# Motor-E2.net
KiCad netlist of a schematic drawn in Altium Designer
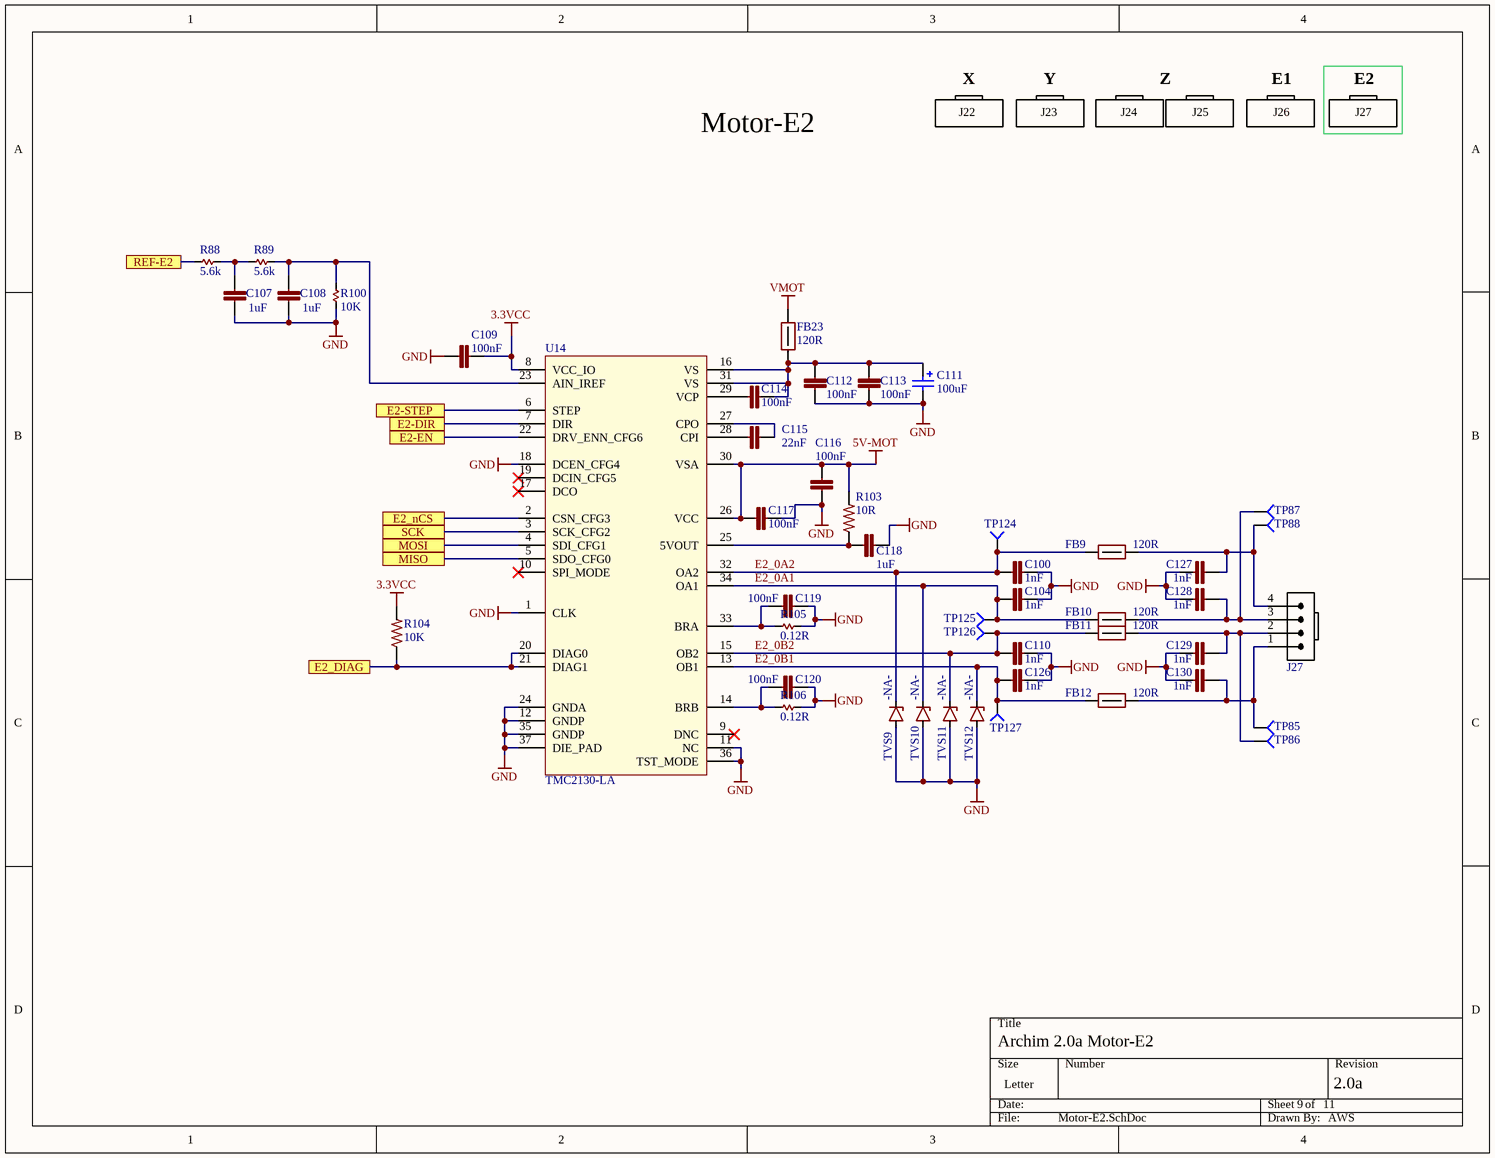
[diagram p0: Motor-E2.SchDoc]

(export (version "E")
  (design (tool "Eeschema 10.0.6"))
  (components
    (comp (ref "C100")
      (value "1nF")
      (footprint "C0402")
      (description "1000pF 50V Ceramic Capacitor X7R 0402 (1005 Metric) 0.039\" L x 0.020\" W (1.00mm x 0.50mm)")
      (fields (field (name "MANUFACTURER") "Murata") (field (name "PART") "1nF 50V X7R 0402"))
      (libsource (lib "3Delight") (part "CAP 1nF 50V 0402 X7R"))
    )
    (comp (ref "C104")
      (value "1nF")
      (footprint "C0402")
      (description "1000pF 50V Ceramic Capacitor X7R 0402 (1005 Metric) 0.039\" L x 0.020\" W (1.00mm x 0.50mm)")
      (fields (field (name "MANUFACTURER") "Murata") (field (name "PART") "1nF 50V X7R 0402"))
      (libsource (lib "3Delight") (part "CAP 1nF 50V 0402 X7R"))
    )
    (comp (ref "C107")
      (value "1uF")
      (footprint "C0402")
      (description "CAP CER 0402 1uF 6.3V 10% X5R")
      (fields (field (name "MANUFACTURER") "Murata") (field (name "PART") "1uF 6.3V X5R 0402"))
      (libsource (lib "") (part "GRM155R60J105KE19D_1"))
    )
    (comp (ref "C108")
      (value "1uF")
      (footprint "C0402")
      (description "CAP CER 0402 1uF 6.3V 10% X5R")
      (fields (field (name "MANUFACTURER") "Murata") (field (name "PART") "1uF 6.3V X5R 0402"))
      (libsource (lib "") (part "GRM155R60J105KE19D_1"))
    )
    (comp (ref "C109")
      (value "100nF")
      (footprint "C0402")
      (description "CAP CER 0402 100nF 16V 10% X7R")
      (fields (field (name "MANUFACTURER") "Murata") (field (name "PART") "0.1uF 16V X7R 0402"))
      (libsource (lib "") (part "GRM155R71C104KA88D_1"))
    )
    (comp (ref "C110")
      (value "1nF")
      (footprint "C0402")
      (description "1000pF 50V Ceramic Capacitor X7R 0402 (1005 Metric) 0.039\" L x 0.020\" W (1.00mm x 0.50mm)")
      (fields (field (name "MANUFACTURER") "Murata") (field (name "PART") "1nF 50V X7R 0402"))
      (libsource (lib "3Delight") (part "CAP 1nF 50V 0402 X7R"))
    )
    (comp (ref "C111")
      (value "100uF")
      (footprint "CAP-ELEC-063063077")
      (description "CAP ALUM 100UF 35V 20% SMD")
      (fields (field (name "MANUFACTURER") "Nichicon") (field (name "PART") "100uF 35V SMD Al-El"))
      (libsource (lib "3Delight") (part "UWT1V101MCL1GS"))
    )
    (comp (ref "C112")
      (value "100nF")
      (footprint "C0603")
      (description "CAP CER 0603 100nF 50V 10% X7R")
      (fields (field (name "MANUFACTURER") "Kemet") (field (name "PART") "100nF 50V X7R 0603"))
      (libsource (lib "3Delight") (part "C0603C104K5RACTU"))
    )
    (comp (ref "C113")
      (value "100nF")
      (footprint "C0603")
      (description "CAP CER 0603 100nF 50V 10% X7R")
      (fields (field (name "MANUFACTURER") "Kemet") (field (name "PART") "100nF 50V X7R 0603"))
      (libsource (lib "3Delight") (part "C0603C104K5RACTU"))
    )
    (comp (ref "C114")
      (value "100nF")
      (footprint "C0603")
      (description "CAP CER 0603 100nF 50V 10% X7R")
      (fields (field (name "MANUFACTURER") "Kemet") (field (name "PART") "100nF 50V X7R 0603"))
      (libsource (lib "") (part "C0603C104K5RACTU_1"))
    )
    (comp (ref "C115")
      (value "22nF")
      (footprint "C0402")
      (description "CAP CER 0402 22nF ±10% 50V X7R")
      (fields (field (name "MANUFACTURER") "YAGEO") (field (name "TOLERANCE") "+/- 10%"))
      (libsource (lib "3Delight") (part "GCM155R71H223KA55D"))
    )
    (comp (ref "C116")
      (value "100nF")
      (footprint "C0402")
      (description "CAP CER 0402 100nF 16V 10% X7R")
      (fields (field (name "MANUFACTURER") "Murata") (field (name "PART") "0.1uF 16V X7R 0402"))
      (libsource (lib "3Delight") (part "GRM155R71C104KA88D"))
    )
    (comp (ref "C117")
      (value "100nF")
      (footprint "C0402")
      (description "CAP CER 0402 100nF 16V 10% X7R")
      (fields (field (name "MANUFACTURER") "Murata") (field (name "PART") "0.1uF 16V X7R 0402"))
      (libsource (lib "") (part "GRM155R71C104KA88D_1"))
    )
    (comp (ref "C118")
      (value "1uF")
      (footprint "C0402")
      (description "CAP CER 0402 1uF 6.3V 10% X5R")
      (fields (field (name "MANUFACTURER") "Murata") (field (name "PART") "1uF 6.3V X5R 0402"))
      (libsource (lib "3Delight") (part "GRM155R60J105KE19D"))
    )
    (comp (ref "C119")
      (value "100nF")
      (footprint "C0603")
      (description "CAP CER 0603 100nF 50V 10% X7R")
      (fields (field (name "MANUFACTURER") "Kemet") (field (name "PART") "100nF 50V X7R 0603"))
      (libsource (lib "") (part "C0603C104K5RACTU_2"))
    )
    (comp (ref "C120")
      (value "100nF")
      (footprint "C0603")
      (description "CAP CER 0603 100nF 50V 10% X7R")
      (fields (field (name "MANUFACTURER") "Kemet") (field (name "PART") "100nF 50V X7R 0603"))
      (libsource (lib "") (part "C0603C104K5RACTU_2"))
    )
    (comp (ref "C126")
      (value "1nF")
      (footprint "C0402")
      (description "1000pF 50V Ceramic Capacitor X7R 0402 (1005 Metric) 0.039\" L x 0.020\" W (1.00mm x 0.50mm)")
      (fields (field (name "MANUFACTURER") "Murata") (field (name "PART") "1nF 50V X7R 0402"))
      (libsource (lib "3Delight") (part "CAP 1nF 50V 0402 X7R"))
    )
    (comp (ref "C127")
      (value "1nF")
      (footprint "C0402")
      (description "1000pF 50V Ceramic Capacitor X7R 0402 (1005 Metric) 0.039\" L x 0.020\" W (1.00mm x 0.50mm)")
      (fields (field (name "MANUFACTURER") "Murata") (field (name "PART") "1nF 50V X7R 0402"))
      (libsource (lib "3Delight") (part "CAP 1nF 50V 0402 X7R"))
    )
    (comp (ref "C128")
      (value "1nF")
      (footprint "C0402")
      (description "1000pF 50V Ceramic Capacitor X7R 0402 (1005 Metric) 0.039\" L x 0.020\" W (1.00mm x 0.50mm)")
      (fields (field (name "MANUFACTURER") "Murata") (field (name "PART") "1nF 50V X7R 0402"))
      (libsource (lib "3Delight") (part "CAP 1nF 50V 0402 X7R"))
    )
    (comp (ref "C129")
      (value "1nF")
      (footprint "C0402")
      (description "1000pF 50V Ceramic Capacitor X7R 0402 (1005 Metric) 0.039\" L x 0.020\" W (1.00mm x 0.50mm)")
      (fields (field (name "MANUFACTURER") "Murata") (field (name "PART") "1nF 50V X7R 0402"))
      (libsource (lib "3Delight") (part "CAP 1nF 50V 0402 X7R"))
    )
    (comp (ref "C130")
      (value "1nF")
      (footprint "C0402")
      (description "1000pF 50V Ceramic Capacitor X7R 0402 (1005 Metric) 0.039\" L x 0.020\" W (1.00mm x 0.50mm)")
      (fields (field (name "MANUFACTURER") "Murata") (field (name "PART") "1nF 50V X7R 0402"))
      (libsource (lib "3Delight") (part "CAP 1nF 50V 0402 X7R"))
    )
    (comp (ref "FB9")
      (value "120R")
      (footprint "FB0603")
      (description "FERRITE BEAD 120 OHM 0603 1LN")
      (fields (field (name "MANUFACTURER") "Samsung") (field (name "PART") "FERRITE 120R 3A 0603"))
      (libsource (lib "3Delight") (part "FERRITE 220R 2.5A 0603"))
    )
    (comp (ref "FB10")
      (value "120R")
      (footprint "FB0603")
      (description "FERRITE BEAD 120 OHM 0603 1LN")
      (fields (field (name "MANUFACTURER") "Samsung") (field (name "PART") "FERRITE 120R 3A 0603"))
      (libsource (lib "3Delight") (part "FERRITE 220R 2.5A 0603"))
    )
    (comp (ref "FB11")
      (value "120R")
      (footprint "FB0603")
      (description "FERRITE BEAD 120 OHM 0603 1LN")
      (fields (field (name "MANUFACTURER") "Samsung") (field (name "PART") "FERRITE 120R 3A 0603"))
      (libsource (lib "3Delight") (part "FERRITE 220R 2.5A 0603"))
    )
    (comp (ref "FB12")
      (value "120R")
      (footprint "FB0603")
      (description "FERRITE BEAD 120 OHM 0603 1LN")
      (fields (field (name "MANUFACTURER") "Samsung") (field (name "PART") "FERRITE 120R 3A 0603"))
      (libsource (lib "3Delight") (part "FERRITE 220R 2.5A 0603"))
    )
    (comp (ref "FB23")
      (value "120R")
      (footprint "FB0603")
      (description "FERRITE BEAD 120 OHM 0603 1LN")
      (fields (field (name "MANUFACTURER") "Samsung") (field (name "PART") "FERRITE 120R 3A 0603"))
      (libsource (lib "Inductors") (part "FERRITE 120R 3A 0603"))
    )
    (comp (ref "J27")
      (value "Molex 0705430038")
      (footprint "4POL254 PIN-IN-PASTE")
      (description "Molex 4 Pin Clip Connector - Pin In Paste footprint")
      (libsource (lib "Connectors") (part "Molex 0705430003 PIP"))
    )
    (comp (ref "R88")
      (value "5.6k")
      (footprint "R0402")
      (description "RES SMD 5.6K OHM 1% 1/16W 0402")
      (fields (field (name "MANUFACTURER") "YAGEO") (field (name "TOLERANCE") "1%"))
      (libsource (lib "Resistors") (part "5.6k 1% 0402"))
    )
    (comp (ref "R89")
      (value "5.6k")
      (footprint "R0402")
      (description "RES SMD 5.6K OHM 1% 1/16W 0402")
      (fields (field (name "MANUFACTURER") "YAGEO") (field (name "TOLERANCE") "1%"))
      (libsource (lib "Resistors") (part "5.6k 1% 0402"))
    )
    (comp (ref "R100")
      (value "10K")
      (footprint "R0402")
      (description "RES SMD 10K OHM 1% 1/16W 0402")
      (fields (field (name "MANUFACTURER") "Yageo") (field (name "PART") "10k 1% 0402"))
      (libsource (lib "Resistors") (part "10k 1% 0402"))
    )
    (comp (ref "R103")
      (value "10R")
      (footprint "R0402")
      (description "RES SMD 10 OHM 1% 1/16W 0402")
      (fields (field (name "MANUFACTURER") "Yageo") (field (name "TOLERANCE") "1%"))
      (libsource (lib "3Delight") (part "RC0402FR-0710RL"))
    )
    (comp (ref "R104")
      (value "10K")
      (footprint "R0402")
      (description "RES SMD 10K OHM 1% 1/16W 0402")
      (fields (field (name "MANUFACTURER") "Yageo") (field (name "PART") "10k 1% 0402"))
      (libsource (lib "3Delight") (part "RC0402FR-0710KP"))
    )
    (comp (ref "R105")
      (value "0.12R")
      (footprint "R1206")
      (description "RES 0.12 OHM 1% 1/2W 1206")
      (fields (field (name "TOLERANCE") "+/- 1%"))
      (libsource (lib "Resistors") (part "0.12R 1% 1206"))
    )
    (comp (ref "R106")
      (value "0.12R")
      (footprint "R1206")
      (description "RES 0.12 OHM 1% 1/2W 1206")
      (fields (field (name "TOLERANCE") "+/- 1%"))
      (libsource (lib "Resistors") (part "0.12R 1% 1206"))
    )
    (comp (ref "TP85")
      (value "TP4")
      (footprint "TP-2")
      (description "Socket")
      (libsource (lib "Archim") (part "Socket"))
    )
    (comp (ref "TP86")
      (value "TP4")
      (footprint "TP-2")
      (description "Socket")
      (libsource (lib "Archim") (part "Socket"))
    )
    (comp (ref "TP87")
      (value "TP4")
      (footprint "TP-2")
      (description "Socket")
      (libsource (lib "Archim") (part "Socket"))
    )
    (comp (ref "TP88")
      (value "TP4")
      (footprint "TP-2")
      (description "Socket")
      (libsource (lib "Archim") (part "Socket"))
    )
    (comp (ref "TP124")
      (value "TP4")
      (footprint "TP-2")
      (description "Socket")
      (libsource (lib "Archim") (part "Socket"))
    )
    (comp (ref "TP125")
      (value "TP4")
      (footprint "TP-2")
      (description "Socket")
      (libsource (lib "Archim") (part "Socket"))
    )
    (comp (ref "TP126")
      (value "TP4")
      (footprint "TP-2")
      (description "Socket")
      (libsource (lib "Archim") (part "Socket"))
    )
    (comp (ref "TP127")
      (value "TP4")
      (footprint "TP-2")
      (description "Socket")
      (libsource (lib "Archim") (part "Socket"))
    )
    (comp (ref "TVS9")
      (value "-NA-")
      (footprint "SMF")
      (description "TVS DIODE 30VWM 48.4VC SMF")
      (fields (field (name "MANUFACTURER") "Vishay") (field (name "PART") "TVS Diode 48.4VC"))
      (libsource (lib "3Delight") (part "TVS 30V SMF"))
    )
    (comp (ref "TVS10")
      (value "-NA-")
      (footprint "SMF")
      (description "TVS DIODE 30VWM 48.4VC SMF")
      (fields (field (name "MANUFACTURER") "Vishay") (field (name "PART") "TVS Diode 48.4VC"))
      (libsource (lib "3Delight") (part "TVS 30V SMF"))
    )
    (comp (ref "TVS11")
      (value "-NA-")
      (footprint "SMF")
      (description "TVS DIODE 30VWM 48.4VC SMF")
      (fields (field (name "MANUFACTURER") "Vishay") (field (name "PART") "TVS Diode 48.4VC"))
      (libsource (lib "3Delight") (part "TVS 30V SMF"))
    )
    (comp (ref "TVS12")
      (value "-NA-")
      (footprint "SMF")
      (description "TVS DIODE 30VWM 48.4VC SMF")
      (fields (field (name "MANUFACTURER") "Vishay") (field (name "PART") "TVS Diode 48.4VC"))
      (libsource (lib "3Delight") (part "TVS 30V SMF"))
    )
    (comp (ref "U14")
      (value "TMC2130-LA")
      (footprint "QFN36-50P500X600X900_HS-37N")
      (description "IC STEPPER MOTOR DVR SPI 36QFN")
      (fields (field (name "MANUFACTURER") "Trinamic") (field (name "PART") "TMC2130"))
      (libsource (lib "ICs-Motor Controller") (part "TMC2130-LA-T"))
    )
  )
  (nets
    (net (code "1") (name "/E2-DIR") (class "Default")
      (node (ref "U14") (pin "7") (pinfunction "DIR_7") (pintype "passive"))
    )
    (net (code "2") (name "/E2-EN") (class "Default")
      (node (ref "U14") (pin "22") (pinfunction "DRV_ENN_CFG6_22") (pintype "passive"))
    )
    (net (code "3") (name "/E2-STEP") (class "Default")
      (node (ref "U14") (pin "6") (pinfunction "STEP_6") (pintype "passive"))
    )
    (net (code "4") (name "/E2_0A1") (class "Default")
      (node (ref "C104") (pin "1") (pinfunction "1_1") (pintype "passive"))
      (node (ref "FB10") (pin "1") (pinfunction "1_1") (pintype "passive"))
      (node (ref "TP125") (pin "1") (pinfunction "1_1") (pintype "passive"))
      (node (ref "TVS10") (pin "K") (pinfunction "K_K") (pintype "passive"))
      (node (ref "U14") (pin "34") (pinfunction "OA1_34") (pintype "passive"))
    )
    (net (code "5") (name "/E2_0A2") (class "Default")
      (node (ref "C100") (pin "1") (pinfunction "1_1") (pintype "passive"))
      (node (ref "FB9") (pin "1") (pinfunction "1_1") (pintype "passive"))
      (node (ref "TP124") (pin "1") (pinfunction "1_1") (pintype "passive"))
      (node (ref "TVS9") (pin "K") (pinfunction "K_K") (pintype "passive"))
      (node (ref "U14") (pin "32") (pinfunction "OA2_32") (pintype "passive"))
    )
    (net (code "6") (name "/E2_0B1") (class "Default")
      (node (ref "C126") (pin "1") (pinfunction "1_1") (pintype "passive"))
      (node (ref "FB12") (pin "1") (pinfunction "1_1") (pintype "passive"))
      (node (ref "TP127") (pin "1") (pinfunction "1_1") (pintype "passive"))
      (node (ref "TVS12") (pin "K") (pinfunction "K_K") (pintype "passive"))
      (node (ref "U14") (pin "13") (pinfunction "OB1_13") (pintype "passive"))
    )
    (net (code "7") (name "/E2_0B2") (class "Default")
      (node (ref "C110") (pin "1") (pinfunction "1_1") (pintype "passive"))
      (node (ref "FB11") (pin "1") (pinfunction "1_1") (pintype "passive"))
      (node (ref "TP126") (pin "1") (pinfunction "1_1") (pintype "passive"))
      (node (ref "TVS11") (pin "K") (pinfunction "K_K") (pintype "passive"))
      (node (ref "U14") (pin "15") (pinfunction "OB2_15") (pintype "passive"))
    )
    (net (code "8") (name "/E2_DIAG") (class "Default")
      (node (ref "R104") (pin "1") (pinfunction "1_1") (pintype "passive"))
      (node (ref "U14") (pin "20") (pinfunction "DIAG0_20") (pintype "passive"))
      (node (ref "U14") (pin "21") (pinfunction "DIAG1_21") (pintype "passive"))
    )
    (net (code "9") (name "/E2_nCS") (class "Default")
      (node (ref "U14") (pin "2") (pinfunction "CSN_CFG3_2") (pintype "passive"))
    )
    (net (code "10") (name "/MISO") (class "Default")
      (node (ref "U14") (pin "5") (pinfunction "SDO_CFG0_5") (pintype "passive"))
    )
    (net (code "11") (name "/MOSI") (class "Default")
      (node (ref "U14") (pin "4") (pinfunction "SDI_CFG1_4") (pintype "passive"))
    )
    (net (code "12") (name "/REF-E2") (class "Default")
      (node (ref "R88") (pin "1") (pinfunction "1_1") (pintype "passive"))
    )
    (net (code "13") (name "/SCK") (class "Default")
      (node (ref "U14") (pin "3") (pinfunction "SCK_CFG2_3") (pintype "passive"))
    )
    (net (code "14") (name "3.3VCC") (class "Default")
      (node (ref "C109") (pin "1") (pinfunction "1_1") (pintype "passive"))
      (node (ref "R104") (pin "2") (pinfunction "2_2") (pintype "passive"))
      (node (ref "U14") (pin "8") (pinfunction "VCC_IO_8") (pintype "passive"))
    )
    (net (code "15") (name "5V-MOT") (class "Default")
      (node (ref "C116") (pin "2") (pinfunction "2_2") (pintype "passive"))
      (node (ref "C117") (pin "2") (pinfunction "2_2") (pintype "passive"))
      (node (ref "R103") (pin "2") (pinfunction "2_2") (pintype "passive"))
      (node (ref "U14") (pin "26") (pinfunction "VCC_26") (pintype "passive"))
      (node (ref "U14") (pin "30") (pinfunction "VSA_30") (pintype "passive"))
    )
    (net (code "16") (name "GND") (class "Default")
      (node (ref "C100") (pin "2") (pinfunction "2_2") (pintype "passive"))
      (node (ref "C104") (pin "2") (pinfunction "2_2") (pintype "passive"))
      (node (ref "C107") (pin "2") (pinfunction "2_2") (pintype "passive"))
      (node (ref "C108") (pin "2") (pinfunction "2_2") (pintype "passive"))
      (node (ref "C109") (pin "2") (pinfunction "2_2") (pintype "passive"))
      (node (ref "C110") (pin "2") (pinfunction "2_2") (pintype "passive"))
      (node (ref "C111") (pin "2") (pinfunction "2_2") (pintype "passive"))
      (node (ref "C112") (pin "1") (pinfunction "1_1") (pintype "passive"))
      (node (ref "C113") (pin "1") (pinfunction "1_1") (pintype "passive"))
      (node (ref "C116") (pin "1") (pinfunction "1_1") (pintype "passive"))
      (node (ref "C117") (pin "1") (pinfunction "1_1") (pintype "passive"))
      (node (ref "C118") (pin "2") (pinfunction "2_2") (pintype "passive"))
      (node (ref "C119") (pin "1") (pinfunction "1_1") (pintype "passive"))
      (node (ref "C120") (pin "1") (pinfunction "1_1") (pintype "passive"))
      (node (ref "C126") (pin "2") (pinfunction "2_2") (pintype "passive"))
      (node (ref "C127") (pin "1") (pinfunction "1_1") (pintype "passive"))
      (node (ref "C128") (pin "1") (pinfunction "1_1") (pintype "passive"))
      (node (ref "C129") (pin "1") (pinfunction "1_1") (pintype "passive"))
      (node (ref "C130") (pin "1") (pinfunction "1_1") (pintype "passive"))
      (node (ref "R100") (pin "1") (pinfunction "1_1") (pintype "passive"))
      (node (ref "R105") (pin "2") (pinfunction "2_2") (pintype "passive"))
      (node (ref "R106") (pin "2") (pinfunction "2_2") (pintype "passive"))
      (node (ref "TVS10") (pin "A") (pinfunction "A_A") (pintype "passive"))
      (node (ref "TVS11") (pin "A") (pinfunction "A_A") (pintype "passive"))
      (node (ref "TVS12") (pin "A") (pinfunction "A_A") (pintype "passive"))
      (node (ref "TVS9") (pin "A") (pinfunction "A_A") (pintype "passive"))
      (node (ref "U14") (pin "1") (pinfunction "CLK_1") (pintype "passive"))
      (node (ref "U14") (pin "11") (pinfunction "NC_11") (pintype "passive"))
      (node (ref "U14") (pin "12") (pinfunction "GNDP_12") (pintype "passive"))
      (node (ref "U14") (pin "18") (pinfunction "DCEN_CFG4_18") (pintype "passive"))
      (node (ref "U14") (pin "24") (pinfunction "GNDA_24") (pintype "passive"))
      (node (ref "U14") (pin "35") (pinfunction "GNDP_35") (pintype "passive"))
      (node (ref "U14") (pin "36") (pinfunction "TST_MODE_36") (pintype "passive"))
      (node (ref "U14") (pin "37") (pinfunction "DIE_PAD_37") (pintype "passive"))
    )
    (net (code "17") (name "Net-(C107-Pad1)") (class "Default")
      (node (ref "C107") (pin "1") (pinfunction "1_1") (pintype "passive"))
      (node (ref "R88") (pin "2") (pinfunction "2_2") (pintype "passive"))
      (node (ref "R89") (pin "1") (pinfunction "1_1") (pintype "passive"))
    )
    (net (code "18") (name "Net-(C111-Pad1)") (class "Default")
      (node (ref "C111") (pin "1") (pinfunction "1_1") (pintype "passive"))
      (node (ref "C112") (pin "2") (pinfunction "2_2") (pintype "passive"))
      (node (ref "C113") (pin "2") (pinfunction "2_2") (pintype "passive"))
      (node (ref "C114") (pin "2") (pinfunction "2_2") (pintype "passive"))
      (node (ref "FB23") (pin "1") (pinfunction "1_1") (pintype "passive"))
      (node (ref "U14") (pin "16") (pinfunction "VS_16") (pintype "passive"))
      (node (ref "U14") (pin "31") (pinfunction "VS_31") (pintype "passive"))
    )
    (net (code "19") (name "Net-(C127-Pad2)") (class "Default")
      (node (ref "C127") (pin "2") (pinfunction "2_2") (pintype "passive"))
      (node (ref "FB9") (pin "2") (pinfunction "2_2") (pintype "passive"))
      (node (ref "J27") (pin "4") (pinfunction "4_4") (pintype "passive"))
      (node (ref "TP88") (pin "1") (pinfunction "1_1") (pintype "passive"))
    )
    (net (code "20") (name "Net-(C128-Pad2)") (class "Default")
      (node (ref "C128") (pin "2") (pinfunction "2_2") (pintype "passive"))
      (node (ref "FB10") (pin "2") (pinfunction "2_2") (pintype "passive"))
      (node (ref "J27") (pin "3") (pinfunction "3_3") (pintype "passive"))
      (node (ref "TP87") (pin "1") (pinfunction "1_1") (pintype "passive"))
    )
    (net (code "21") (name "Net-(C129-Pad2)") (class "Default")
      (node (ref "C129") (pin "2") (pinfunction "2_2") (pintype "passive"))
      (node (ref "FB11") (pin "2") (pinfunction "2_2") (pintype "passive"))
      (node (ref "J27") (pin "2") (pinfunction "2_2") (pintype "passive"))
      (node (ref "TP86") (pin "1") (pinfunction "1_1") (pintype "passive"))
    )
    (net (code "22") (name "Net-(C130-Pad2)") (class "Default")
      (node (ref "C130") (pin "2") (pinfunction "2_2") (pintype "passive"))
      (node (ref "FB12") (pin "2") (pinfunction "2_2") (pintype "passive"))
      (node (ref "J27") (pin "1") (pinfunction "1_1") (pintype "passive"))
      (node (ref "TP85") (pin "1") (pinfunction "1_1") (pintype "passive"))
    )
    (net (code "23") (name "Net-(U14-5VOUT)") (class "Default")
      (node (ref "C118") (pin "1") (pinfunction "1_1") (pintype "passive"))
      (node (ref "R103") (pin "1") (pinfunction "1_1") (pintype "passive"))
      (node (ref "U14") (pin "25") (pinfunction "5VOUT_25") (pintype "passive"))
    )
    (net (code "24") (name "Net-(U14-AIN_IREF)") (class "Default")
      (node (ref "C108") (pin "1") (pinfunction "1_1") (pintype "passive"))
      (node (ref "R100") (pin "2") (pinfunction "2_2") (pintype "passive"))
      (node (ref "R89") (pin "2") (pinfunction "2_2") (pintype "passive"))
      (node (ref "U14") (pin "23") (pinfunction "AIN_IREF_23") (pintype "passive"))
    )
    (net (code "25") (name "Net-(U14-BRA)") (class "Default")
      (node (ref "C119") (pin "2") (pinfunction "2_2") (pintype "passive"))
      (node (ref "R105") (pin "1") (pinfunction "1_1") (pintype "passive"))
      (node (ref "U14") (pin "33") (pinfunction "BRA_33") (pintype "passive"))
    )
    (net (code "26") (name "Net-(U14-BRB)") (class "Default")
      (node (ref "C120") (pin "2") (pinfunction "2_2") (pintype "passive"))
      (node (ref "R106") (pin "1") (pinfunction "1_1") (pintype "passive"))
      (node (ref "U14") (pin "14") (pinfunction "BRB_14") (pintype "passive"))
    )
    (net (code "27") (name "Net-(U14-CPI)") (class "Default")
      (node (ref "C115") (pin "1") (pinfunction "1_1") (pintype "passive"))
      (node (ref "U14") (pin "28") (pinfunction "CPI_28") (pintype "passive"))
    )
    (net (code "28") (name "Net-(U14-CPO)") (class "Default")
      (node (ref "C115") (pin "2") (pinfunction "2_2") (pintype "passive"))
      (node (ref "U14") (pin "27") (pinfunction "CPO_27") (pintype "passive"))
    )
    (net (code "29") (name "Net-(U14-VCP)") (class "Default")
      (node (ref "C114") (pin "1") (pinfunction "1_1") (pintype "passive"))
      (node (ref "U14") (pin "29") (pinfunction "VCP_29") (pintype "passive"))
    )
    (net (code "30") (name "VMOT") (class "Default")
      (node (ref "FB23") (pin "2") (pinfunction "2_2") (pintype "passive"))
    )
    (net (code "31") (name "unconnected-(U14-DCIN_CFG5-Pad19)") (class "Default")
      (node (ref "U14") (pin "19") (pinfunction "DCIN_CFG5_19") (pintype "passive+no_connect"))
    )
    (net (code "32") (name "unconnected-(U14-DCO-Pad17)") (class "Default")
      (node (ref "U14") (pin "17") (pinfunction "DCO_17") (pintype "passive+no_connect"))
    )
    (net (code "33") (name "unconnected-(U14-DNC-Pad9)") (class "Default")
      (node (ref "U14") (pin "9") (pinfunction "DNC_9") (pintype "passive+no_connect"))
    )
    (net (code "34") (name "unconnected-(U14-SPI_MODE-Pad10)") (class "Default")
      (node (ref "U14") (pin "10") (pinfunction "SPI_MODE_10") (pintype "passive+no_connect"))
    )
  )
)
